# M5TeslaCoilTuner.net
KiCad netlist of a schematic drawn in Altium Designer
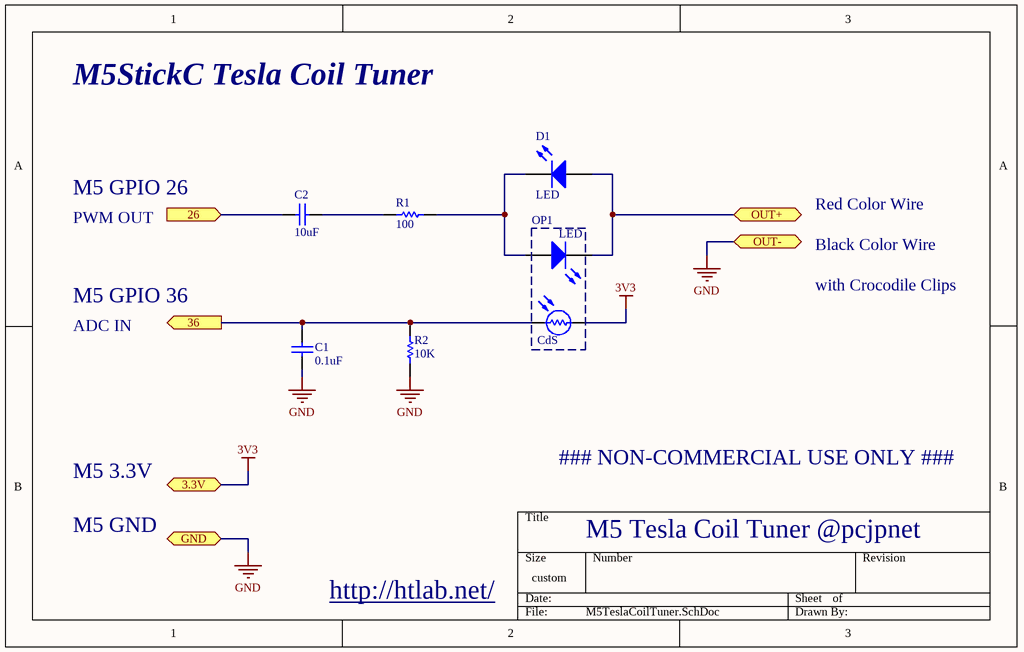
[diagram p0: M5TeslaCoilTuner.SchDoc]

(export (version "E")
  (design (tool "Eeschema 10.0.6"))
  (components
    (comp (ref "C1")
      (value "0.1uF")
      (footprint "RAD-0.3")
      (description "Capacitor")
      (fields (field (name "PUBLISHER") "Altium Limited"))
      (libsource (lib "TeslaCoilTuner_lib") (part "Cap"))
    )
    (comp (ref "C2")
      (value "10uF")
      (footprint "RAD-0.3")
      (description "Capacitor")
      (fields (field (name "PUBLISHER") "Altium Limited"))
      (libsource (lib "TeslaCoilTuner_lib") (part "Cap"))
    )
    (comp (ref "D1")
      (value "LED")
      (footprint "LED-1")
      (description "Typical RED GaAs LED")
      (fields (field (name "PUBLISHER") "Altium Limited"))
      (libsource (lib "TeslaCoilTuner_lib") (part "LED1"))
    )
    (comp (ref "OP1")
      (value "LED")
      (footprint "LED-1")
      (description "Typical RED GaAs LED")
      (fields (field (name "PUBLISHER") "Altium Limited"))
      (libsource (lib "TeslaCoilTuner_lib") (part "LED1"))
    )
    (comp (ref "OP2")
      (value "CdS")
      (footprint "AXIAL-0.3")
      (description "Resistor")
      (fields (field (name "PUBLISHER") "Altium Limited"))
      (libsource (lib "TeslaCoilTuner_lib") (part "CdS"))
    )
    (comp (ref "R1")
      (value "100")
      (footprint "AXIAL-0.3")
      (description "Resistor")
      (fields (field (name "PUBLISHER") "Altium Limited"))
      (libsource (lib "TeslaCoilTuner_lib") (part "Res1"))
    )
    (comp (ref "R2")
      (value "10K")
      (footprint "AXIAL-0.3")
      (description "Resistor")
      (fields (field (name "PUBLISHER") "Altium Limited"))
      (libsource (lib "TeslaCoilTuner_lib") (part "Res1"))
    )
  )
  (nets
    (net (code "1") (name "/26") (class "Default")
      (node (ref "C2") (pin "1") (pinfunction "1_1") (pintype "passive"))
    )
    (net (code "2") (name "/36") (class "Default")
      (node (ref "C1") (pin "2") (pinfunction "2_2") (pintype "passive"))
      (node (ref "OP2") (pin "1") (pinfunction "1_1") (pintype "passive"))
      (node (ref "R2") (pin "2") (pinfunction "2_2") (pintype "passive"))
    )
    (net (code "3") (name "/OUT+") (class "Default")
      (node (ref "D1") (pin "1") (pinfunction "A_1") (pintype "passive"))
      (node (ref "OP1") (pin "2") (pinfunction "K_2") (pintype "passive"))
    )
    (net (code "4") (name "3V3") (class "Default")
      (node (ref "OP2") (pin "2") (pinfunction "2_2") (pintype "passive"))
    )
    (net (code "5") (name "GND") (class "Default")
      (node (ref "C1") (pin "1") (pinfunction "1_1") (pintype "passive"))
      (node (ref "R2") (pin "1") (pinfunction "1_1") (pintype "passive"))
    )
    (net (code "6") (name "Net-(C2-Pad2)") (class "Default")
      (node (ref "C2") (pin "2") (pinfunction "2_2") (pintype "passive"))
      (node (ref "R1") (pin "1") (pinfunction "1_1") (pintype "passive"))
    )
    (net (code "7") (name "Net-(D1-K)") (class "Default")
      (node (ref "D1") (pin "2") (pinfunction "K_2") (pintype "passive"))
      (node (ref "OP1") (pin "1") (pinfunction "A_1") (pintype "passive"))
      (node (ref "R1") (pin "2") (pinfunction "2_2") (pintype "passive"))
    )
  )
)
